# PART-04-_R200-249.net
KiCad netlist of a schematic drawn in Altium Designer
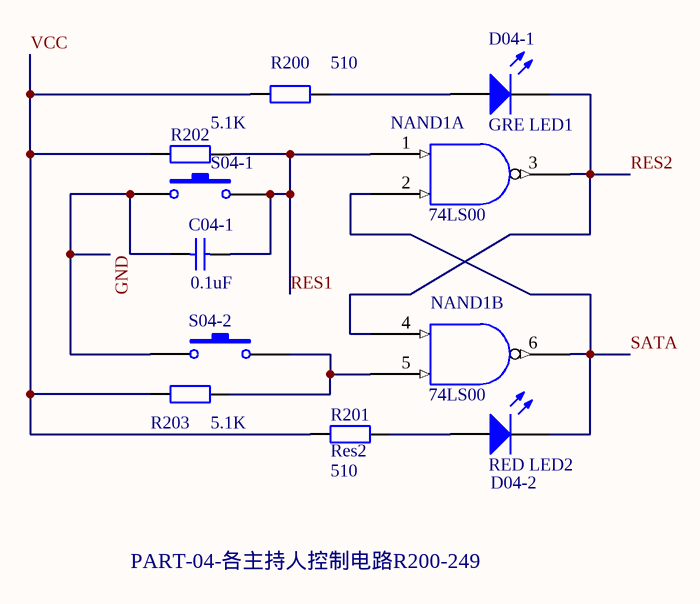
[diagram p0: PART-04-各主持人控制电路R200-249.SchDoc]

(export (version "E")
  (design (tool "Eeschema 10.0.6"))
  (components
    (comp (ref "C04-1")
      (value "0.1uF")
      (footprint "RAD-0.3")
      (description "Capacitor")
      (fields (field (name "Comment") "Cap") (field (name "PUBLISHER") "Altium Limited"))
      (libsource (lib "Miscellaneous Devices") (part "Cap"))
    )
    (comp (ref "D04-1")
      (value "GRE LED1")
      (footprint "LED-1")
      (description "Typical RED GaAs LED")
      (fields (field (name "PUBLISHER") "Altium Limited"))
      (libsource (lib "Miscellaneous Devices") (part "LED1"))
    )
    (comp (ref "D04-2")
      (value "RED LED2")
      (footprint "LED-1")
      (description "Typical RED GaAs LED")
      (fields (field (name "PUBLISHER") "Altium Limited"))
      (libsource (lib "Miscellaneous Devices") (part "LED1"))
    )
    (comp (ref "NAND1")
      (value "74LS00")
      (footprint "DIP-14")
      (libsource (lib "Schematic TTL") (part "74LS00"))
    )
    (comp (ref "R200")
      (value "510")
      (footprint "AXIAL-0.4")
      (description "Resistor")
      (fields (field (name "Comment") "Res2") (field (name "PUBLISHER") "Altium Limited"))
      (libsource (lib "Miscellaneous Devices") (part "Res2"))
    )
    (comp (ref "R201")
      (value "Res2")
      (footprint "AXIAL-0.4")
      (description "Resistor")
      (fields (field (name "ALTIUM_VALUE") "510") (field (name "PUBLISHER") "Altium Limited"))
      (libsource (lib "Miscellaneous Devices") (part "Res2"))
    )
    (comp (ref "R202")
      (value "5.1K")
      (footprint "AXIAL-0.4")
      (description "Resistor")
      (fields (field (name "Comment") "Res2") (field (name "PUBLISHER") "Altium Limited"))
      (libsource (lib "Miscellaneous Devices") (part "Res2"))
    )
    (comp (ref "R203")
      (value "5.1K")
      (footprint "AXIAL-0.4")
      (description "Resistor")
      (fields (field (name "Comment") "Res2") (field (name "PUBLISHER") "Altium Limited"))
      (libsource (lib "Miscellaneous Devices") (part "Res2"))
    )
    (comp (ref "S04-1")
      (value "SW-PB")
      (footprint "SPST-2")
      (description "Switch")
      (fields (field (name "PUBLISHER") "Altium Limited"))
      (libsource (lib "Miscellaneous Devices") (part "SW-PB"))
    )
    (comp (ref "S04-2")
      (value "SW-PB")
      (footprint "SPST-2")
      (description "Switch")
      (fields (field (name "PUBLISHER") "Altium Limited"))
      (libsource (lib "Miscellaneous Devices") (part "SW-PB"))
    )
  )
  (nets
    (net (code "1") (name "/RES1") (class "Default")
      (node (ref "C04-1") (pin "2") (pinfunction "2_2") (pintype "passive"))
      (node (ref "NAND1") (pin "1") (pintype "input"))
      (node (ref "R202") (pin "2") (pinfunction "2_2") (pintype "passive"))
      (node (ref "S04-1") (pin "2") (pinfunction "2_2") (pintype "passive"))
    )
    (net (code "2") (name "/RES2") (class "Default")
      (node (ref "D04-1") (pin "2") (pinfunction "K_2") (pintype "passive"))
      (node (ref "NAND1") (pin "3") (pintype "output"))
      (node (ref "NAND1") (pin "4") (pintype "input"))
    )
    (net (code "3") (name "/SATA") (class "Default")
      (node (ref "D04-2") (pin "2") (pinfunction "K_2") (pintype "passive"))
      (node (ref "NAND1") (pin "2") (pintype "input"))
      (node (ref "NAND1") (pin "6") (pintype "output"))
    )
    (net (code "4") (name "GND") (class "Default")
      (node (ref "C04-1") (pin "1") (pinfunction "1_1") (pintype "passive"))
      (node (ref "NAND1") (pin "7") (pinfunction "GND_7") (pintype "power_in"))
      (node (ref "S04-1") (pin "1") (pinfunction "1_1") (pintype "passive"))
      (node (ref "S04-2") (pin "1") (pinfunction "1_1") (pintype "passive"))
    )
    (net (code "5") (name "Net-(D04-1-A)") (class "Default")
      (node (ref "D04-1") (pin "1") (pinfunction "A_1") (pintype "passive"))
      (node (ref "R200") (pin "2") (pinfunction "2_2") (pintype "passive"))
    )
    (net (code "6") (name "Net-(D04-2-A)") (class "Default")
      (node (ref "D04-2") (pin "1") (pinfunction "A_1") (pintype "passive"))
      (node (ref "R201") (pin "2") (pinfunction "2_2") (pintype "passive"))
    )
    (net (code "7") (name "Net-(NAND1-Pad5)") (class "Default")
      (node (ref "NAND1") (pin "5") (pintype "input"))
      (node (ref "R203") (pin "2") (pinfunction "2_2") (pintype "passive"))
      (node (ref "S04-2") (pin "2") (pinfunction "2_2") (pintype "passive"))
    )
    (net (code "8") (name "VCC") (class "Default")
      (node (ref "NAND1") (pin "14") (pinfunction "VCC_14") (pintype "power_in"))
      (node (ref "R200") (pin "1") (pinfunction "1_1") (pintype "passive"))
      (node (ref "R201") (pin "1") (pinfunction "1_1") (pintype "passive"))
      (node (ref "R202") (pin "1") (pinfunction "1_1") (pintype "passive"))
      (node (ref "R203") (pin "1") (pinfunction "1_1") (pintype "passive"))
    )
  )
)
